# badge2.net
KiCad netlist of a schematic drawn in Altium Designer
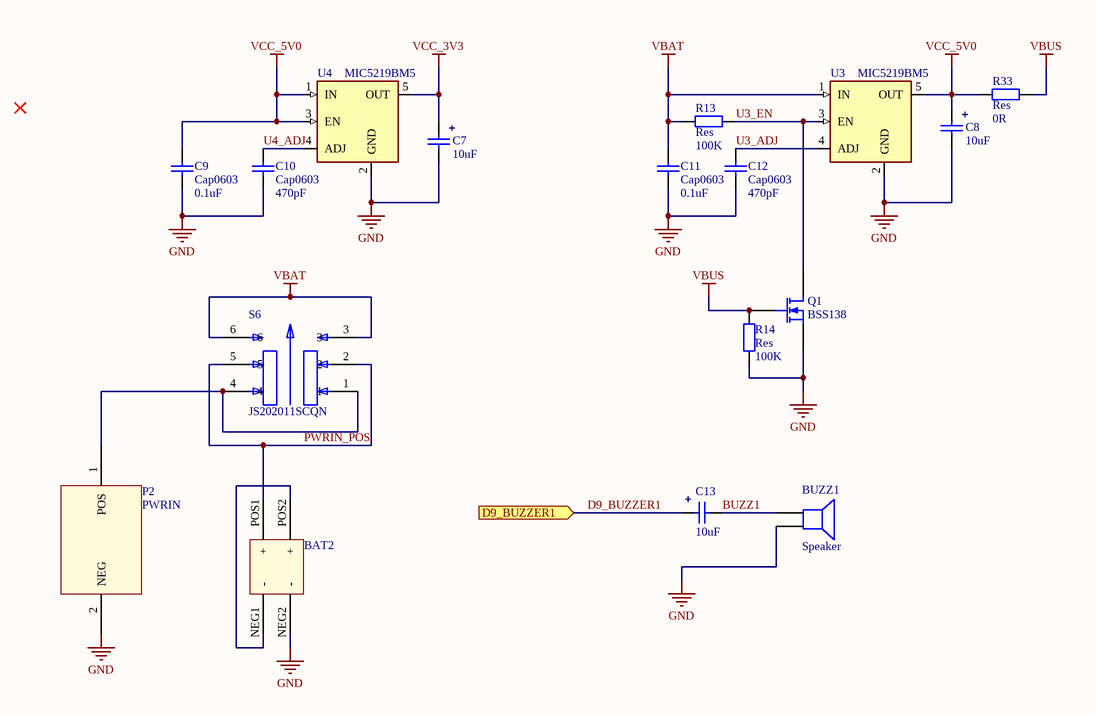
[diagram p0: badge2.SchDoc]

(export (version "E")
  (design (tool "Eeschema 10.0.6"))
  (components
    (comp (ref "BAT2")
      (value "BATT_18650x2")
      (footprint "BATT_18650x2")
      (fields (field (name "MF") "DNP"))
      (libsource (lib "badge") (part "BATT_18650x2"))
    )
    (comp (ref "BUZZ1")
      (value "Speaker")
      (footprint "SMC")
      (description "Loudspeaker")
      (fields (field (name "MF") "DNP") (field (name "PUBLISHER") "Altium Limited"))
      (libsource (lib "badge") (part "Speaker"))
    )
    (comp (ref "C7")
      (value "10uF")
      (footprint "C1206 _POL")
      (description "Capacitor")
      (fields
        (field (name "MF") "KEMET")
        (field (name "MP") "T491A106K010AT")
        (field (name "PUBLISHER") "Altium Limited")
      )
      (libsource (lib "badge") (part "CapPol"))
    )
    (comp (ref "C8")
      (value "10uF")
      (footprint "C1206 _POL")
      (description "Capacitor")
      (fields
        (field (name "MF") "KEMET")
        (field (name "MP") "T491A106K010AT")
        (field (name "PUBLISHER") "Altium Limited")
      )
      (libsource (lib "badge") (part "CapPol"))
    )
    (comp (ref "C9")
      (value "Cap0603")
      (footprint "C0603")
      (description "Capacitor")
      (fields
        (field (name "ALTIUM_VALUE") "0.1uF")
        (field (name "MF") "KEMET")
        (field (name "MP") "C0603C104Z3VACTU")
        (field (name "PUBLISHER") "Altium Limited")
      )
      (libsource (lib "badge") (part "Cap0603"))
    )
    (comp (ref "C10")
      (value "Cap0603")
      (footprint "C0603")
      (description "Capacitor")
      (fields
        (field (name "ALTIUM_VALUE") "470pF")
        (field (name "MF") "KEMET")
        (field (name "MP") "C0603C471J1GACTU")
        (field (name "PUBLISHER") "Altium Limited")
      )
      (libsource (lib "badge") (part "Cap0603"))
    )
    (comp (ref "C11")
      (value "Cap0603")
      (footprint "C0603")
      (description "Capacitor")
      (fields
        (field (name "ALTIUM_VALUE") "0.1uF")
        (field (name "MF") "KEMET")
        (field (name "MP") "C0603C104M4RACTU")
        (field (name "PUBLISHER") "Altium Limited")
      )
      (libsource (lib "badge") (part "Cap0603"))
    )
    (comp (ref "C12")
      (value "Cap0603")
      (footprint "C0603")
      (description "Capacitor")
      (fields
        (field (name "ALTIUM_VALUE") "470pF")
        (field (name "MF") "KEMET")
        (field (name "MP") "C0603C471J1GACTU")
        (field (name "PUBLISHER") "Altium Limited")
      )
      (libsource (lib "badge") (part "Cap0603"))
    )
    (comp (ref "C13")
      (value "10uF")
      (footprint "C1206 _POL")
      (description "Capacitor")
      (fields
        (field (name "MF") "KEMET")
        (field (name "MP") "T491A106K010AT")
        (field (name "PUBLISHER") "Altium Limited")
      )
      (libsource (lib "badge") (part "CapPol"))
    )
    (comp (ref "P2")
      (value "PWRIN")
      (footprint "PWRIN")
      (fields (field (name "MF") "Molex") (field (name "MP") "S2B-PH-SM4-TB(LF)(SN)"))
      (libsource (lib "badge") (part "PWRIN"))
    )
    (comp (ref "Q1")
      (value "BSS138")
      (footprint "SOT23_N")
      (description "N-Channel MOSFET")
      (fields
        (field (name "MF") "ON Semiconductor")
        (field (name "MP") "ATSAMD11C14A-SSNTDKR-ND")
        (field (name "PUBLISHER") "Altium Limited")
      )
      (libsource (lib "badge") (part "MOSFET-N"))
    )
    (comp (ref "R13")
      (value "Res")
      (footprint "R0603")
      (description "Resistor")
      (fields
        (field (name "ALTIUM_VALUE") "100K")
        (field (name "MF") "Yageo")
        (field (name "MP") "RC0603JR-07100KL")
        (field (name "PUBLISHER") "Altium Limited")
      )
      (libsource (lib "badge") (part "Res"))
    )
    (comp (ref "R14")
      (value "Res")
      (footprint "R0603")
      (description "Resistor")
      (fields
        (field (name "ALTIUM_VALUE") "100K")
        (field (name "MF") "Yageo")
        (field (name "MP") "RC0603JR-07100KL")
        (field (name "PUBLISHER") "Altium Limited")
      )
      (libsource (lib "") (part "Res_1"))
    )
    (comp (ref "R33")
      (value "Res")
      (footprint "R0603")
      (description "Resistor")
      (fields
        (field (name "ALTIUM_VALUE") "0R")
        (field (name "MF") "Yageo")
        (field (name "MP") "RC0603JR-070RL")
        (field (name "PUBLISHER") "Altium Limited")
      )
      (libsource (lib "badge") (part "Res"))
    )
    (comp (ref "S6")
      (value "JS202011SCQN")
      (footprint "SW_JS202011SCQN")
      (description "Slide Switch DPDT Surface Mount")
      (fields (field (name "DIGI-KEY_PART_NUMBER") "401-2002-1-ND") (field (name "MF") "C&K"))
      (libsource (lib "badge") (part "JS202011SCQN"))
    )
    (comp (ref "U3")
      (value "MIC5219BM5")
      (footprint "SOT23-5_N")
      (description "Linear Voltage Regulator IC 1 Output 500mA SOT-23-5")
      (fields (field (name "MF") "Micrel"))
      (libsource (lib "badge") (part "MIC5219BM5"))
    )
    (comp (ref "U4")
      (value "MIC5219BM5")
      (footprint "SOT23-5_N")
      (description "Linear Voltage Regulator IC 1 Output 500mA SOT-23-5")
      (fields (field (name "MF") "Micrel"))
      (libsource (lib "badge") (part "MIC5219BM5"))
    )
  )
  (nets
    (net (code "1") (name "/BUZZ1") (class "Default")
      (node (ref "BUZZ1") (pin "1") (pinfunction "1_1") (pintype "passive"))
      (node (ref "C13") (pin "2") (pinfunction "2_2") (pintype "passive"))
    )
    (net (code "2") (name "/D9_BUZZER1") (class "Default")
      (node (ref "C13") (pin "1") (pinfunction "1_1") (pintype "passive"))
    )
    (net (code "3") (name "/PWRIN_POS") (class "Default")
      (node (ref "BAT2") (pin "POS1") (pinfunction "+_POS1") (pintype "passive"))
      (node (ref "S6") (pin "2") (pinfunction "2_2") (pintype "passive"))
      (node (ref "S6") (pin "5") (pinfunction "5_5") (pintype "passive"))
    )
    (net (code "4") (name "/U3_ADJ") (class "Default")
      (node (ref "C12") (pin "2") (pinfunction "2_2") (pintype "passive"))
      (node (ref "U3") (pin "4") (pinfunction "ADJ_4") (pintype "passive"))
    )
    (net (code "5") (name "/U3_EN") (class "Default")
      (node (ref "Q1") (pin "1") (pinfunction "D_1") (pintype "passive"))
      (node (ref "R13") (pin "2") (pinfunction "2_2") (pintype "passive"))
      (node (ref "U3") (pin "3") (pinfunction "EN_3") (pintype "input"))
    )
    (net (code "6") (name "/U4_ADJ") (class "Default")
      (node (ref "C10") (pin "2") (pinfunction "2_2") (pintype "passive"))
      (node (ref "U4") (pin "4") (pinfunction "ADJ_4") (pintype "passive"))
    )
    (net (code "7") (name "GND") (class "Default")
      (node (ref "BAT2") (pin "NEG2") (pinfunction "-_NEG2") (pintype "passive"))
      (node (ref "BUZZ1") (pin "2") (pinfunction "2_2") (pintype "passive"))
      (node (ref "C10") (pin "1") (pinfunction "1_1") (pintype "passive"))
      (node (ref "C11") (pin "1") (pinfunction "1_1") (pintype "passive"))
      (node (ref "C12") (pin "1") (pinfunction "1_1") (pintype "passive"))
      (node (ref "C7") (pin "2") (pinfunction "2_2") (pintype "passive"))
      (node (ref "C8") (pin "2") (pinfunction "2_2") (pintype "passive"))
      (node (ref "C9") (pin "1") (pinfunction "1_1") (pintype "passive"))
      (node (ref "P2") (pin "2") (pinfunction "NEG_2") (pintype "power_in"))
      (node (ref "Q1") (pin "2") (pinfunction "S_2") (pintype "passive"))
      (node (ref "R14") (pin "1") (pinfunction "1_1") (pintype "passive"))
      (node (ref "U3") (pin "2") (pinfunction "GND_2") (pintype "power_in"))
      (node (ref "U4") (pin "2") (pinfunction "GND_2") (pintype "power_in"))
    )
    (net (code "8") (name "Net-(BAT2-+-PadPOS2)") (class "Default")
      (node (ref "BAT2") (pin "NEG1") (pinfunction "-_NEG1") (pintype "passive"))
      (node (ref "BAT2") (pin "POS2") (pinfunction "+_POS2") (pintype "passive"))
    )
    (net (code "9") (name "Net-(P2-POS)") (class "Default")
      (node (ref "P2") (pin "1") (pinfunction "POS_1") (pintype "power_in"))
      (node (ref "S6") (pin "1") (pinfunction "1_1") (pintype "passive"))
      (node (ref "S6") (pin "4") (pinfunction "4_4") (pintype "passive"))
    )
    (net (code "10") (name "VBAT") (class "Default")
      (node (ref "C11") (pin "2") (pinfunction "2_2") (pintype "passive"))
      (node (ref "R13") (pin "1") (pinfunction "1_1") (pintype "passive"))
      (node (ref "S6") (pin "3") (pinfunction "3_3") (pintype "passive"))
      (node (ref "S6") (pin "6") (pinfunction "6_6") (pintype "passive"))
      (node (ref "U3") (pin "1") (pinfunction "IN_1") (pintype "input"))
    )
    (net (code "11") (name "VBUS") (class "Default")
      (node (ref "Q1") (pin "3") (pinfunction "G_3") (pintype "passive"))
      (node (ref "R14") (pin "2") (pinfunction "2_2") (pintype "passive"))
      (node (ref "R33") (pin "2") (pinfunction "2_2") (pintype "passive"))
    )
    (net (code "12") (name "VCC_3V3") (class "Default")
      (node (ref "C7") (pin "1") (pinfunction "1_1") (pintype "passive"))
      (node (ref "U4") (pin "5") (pinfunction "OUT_5") (pintype "power_in"))
    )
    (net (code "13") (name "VCC_5V0") (class "Default")
      (node (ref "C8") (pin "1") (pinfunction "1_1") (pintype "passive"))
      (node (ref "C9") (pin "2") (pinfunction "2_2") (pintype "passive"))
      (node (ref "R33") (pin "1") (pinfunction "1_1") (pintype "passive"))
      (node (ref "U3") (pin "5") (pinfunction "OUT_5") (pintype "power_in"))
      (node (ref "U4") (pin "1") (pinfunction "IN_1") (pintype "input"))
      (node (ref "U4") (pin "3") (pinfunction "EN_3") (pintype "input"))
    )
  )
)
